# iPot.net
KiCad netlist of a schematic drawn in EAGLE
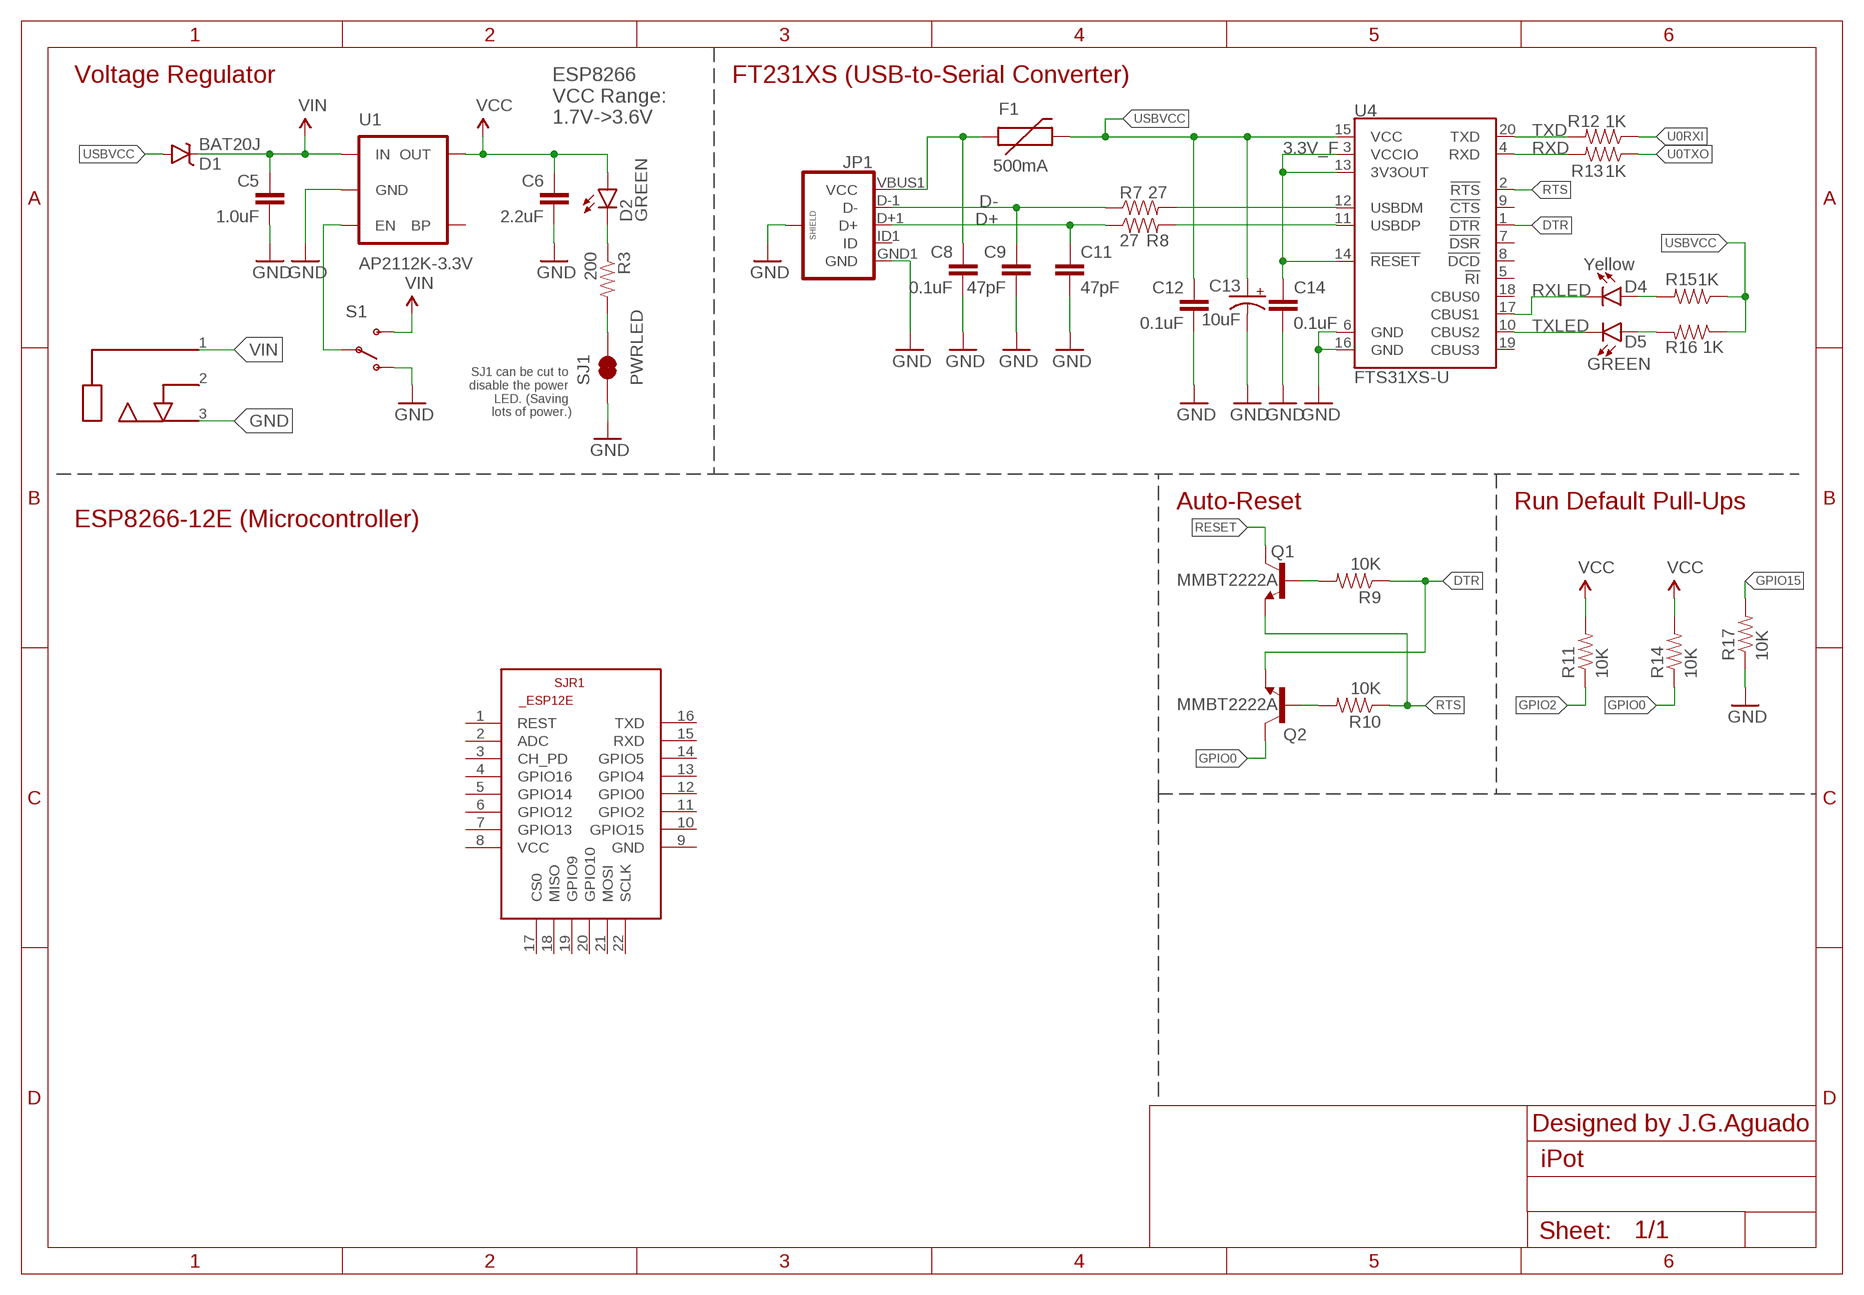
[diagram p0: schematic, sheet 1]

(export (version "E")
  (design (tool "Eeschema 10.0.6"))
  (components
    (comp (ref "C5")
      (value "1.0uF")
      (footprint "eagle-import:0805")
      (libsource (lib "eagle-import") (part "1.0UF-25V-+80/-20(0805)"))
    )
    (comp (ref "C6")
      (value "2.2uF")
      (footprint "eagle-import:0603-CAP")
      (libsource (lib "eagle-import") (part "2.2UF-10V-20%(0603)"))
    )
    (comp (ref "C8")
      (value "0.1uF")
      (footprint "eagle-import:0603-CAP")
      (libsource (lib "eagle-import") (part "0.1UF-25V(+80/-20%)(0603)"))
    )
    (comp (ref "C9")
      (value "47pF")
      (footprint "eagle-import:0603-CAP")
      (libsource (lib "eagle-import") (part "47PF-50V-5%(0603)"))
    )
    (comp (ref "C11")
      (value "47pF")
      (footprint "eagle-import:0603-CAP")
      (libsource (lib "eagle-import") (part "47PF-50V-5%(0603)"))
    )
    (comp (ref "C12")
      (value "0.1uF")
      (footprint "eagle-import:0603-CAP")
      (libsource (lib "eagle-import") (part "0.1UF-25V(+80/-20%)(0603)"))
    )
    (comp (ref "C13")
      (value "10uF")
      (footprint "eagle-import:EIA3216")
      (libsource (lib "eagle-import") (part "10UF-16V-10%(TANT)"))
    )
    (comp (ref "C14")
      (value "0.1uF")
      (footprint "eagle-import:0603-CAP")
      (libsource (lib "eagle-import") (part "0.1UF-25V(+80/-20%)(0603)"))
    )
    (comp (ref "D1")
      (value "BAT20J")
      (footprint "eagle-import:SOD-323")
      (libsource (lib "eagle-import") (part "DIODE-SCHOTTKY-BAT20J"))
    )
    (comp (ref "D2")
      (value "GREEN")
      (footprint "eagle-import:LED-0603")
      (libsource (lib "eagle-import") (part "LED-RED0603"))
    )
    (comp (ref "D4")
      (value "Yellow")
      (footprint "eagle-import:LED-0603")
      (libsource (lib "eagle-import") (part "LED-YELLOW0603"))
    )
    (comp (ref "D5")
      (value "GREEN")
      (footprint "eagle-import:LED-0603")
      (libsource (lib "eagle-import") (part "LED-GREEN0603"))
    )
    (comp (ref "F1")
      (value "500mA")
      (footprint "eagle-import:PTC-1206")
      (libsource (lib "eagle-import") (part "PTCSMD"))
    )
    (comp (ref "JP1")
      (value "USB_MICROB_PLUGCONN-11752")
      (footprint "eagle-import:USB-B-MICRO-SMD_V03")
      (libsource (lib "eagle-import") (part "USB_MICROB_PLUGCONN-11752"))
    )
    (comp (ref "JP2")
      (value "DC_JACK_1.3")
      (footprint "eagle-import:DC_JACK_1.3")
      (libsource (lib "eagle-import") (part "DC_JACK_1.3"))
    )
    (comp (ref "Q1")
      (value "MMBT2222A")
      (footprint "eagle-import:SOT23-3")
      (libsource (lib "eagle-import") (part "TRANSISTOR_NPNMMBT2222A"))
    )
    (comp (ref "Q2")
      (value "MMBT2222A")
      (footprint "eagle-import:SOT23-3")
      (libsource (lib "eagle-import") (part "TRANSISTOR_NPNMMBT2222A"))
    )
    (comp (ref "R3")
      (value "200")
      (footprint "eagle-import:0603-RES")
      (libsource (lib "eagle-import") (part "200OHM1/10W1%(0603)"))
    )
    (comp (ref "R7")
      (value "27")
      (footprint "eagle-import:0603-RES")
      (libsource (lib "eagle-import") (part "27OHM1/10W1%(0603)0603-RES"))
    )
    (comp (ref "R8")
      (value "27")
      (footprint "eagle-import:0603-RES")
      (libsource (lib "eagle-import") (part "27OHM1/10W1%(0603)0603-RES"))
    )
    (comp (ref "R9")
      (value "10K")
      (footprint "eagle-import:0603-RES")
      (libsource (lib "eagle-import") (part "10KOHM1/10W1%(0603)0603"))
    )
    (comp (ref "R10")
      (value "10K")
      (footprint "eagle-import:0603-RES")
      (libsource (lib "eagle-import") (part "10KOHM1/10W1%(0603)0603"))
    )
    (comp (ref "R11")
      (value "10K")
      (footprint "eagle-import:0603-RES")
      (libsource (lib "eagle-import") (part "10KOHM1/10W1%(0603)0603"))
    )
    (comp (ref "R12")
      (value "1K")
      (footprint "eagle-import:0603-RES")
      (libsource (lib "eagle-import") (part "1KOHM-1/10W-1%(0603)"))
    )
    (comp (ref "R13")
      (value "1K")
      (footprint "eagle-import:0603-RES")
      (libsource (lib "eagle-import") (part "1KOHM-1/10W-1%(0603)"))
    )
    (comp (ref "R14")
      (value "10K")
      (footprint "eagle-import:0603-RES")
      (libsource (lib "eagle-import") (part "10KOHM1/10W1%(0603)0603"))
    )
    (comp (ref "R15")
      (value "1K")
      (footprint "eagle-import:0603-RES")
      (libsource (lib "eagle-import") (part "1KOHM-1/10W-1%(0603)"))
    )
    (comp (ref "R16")
      (value "1K")
      (footprint "eagle-import:0603-RES")
      (libsource (lib "eagle-import") (part "1KOHM-1/10W-1%(0603)"))
    )
    (comp (ref "R17")
      (value "10K")
      (footprint "eagle-import:0603-RES")
      (libsource (lib "eagle-import") (part "10KOHM1/10W1%(0603)0603"))
    )
    (comp (ref "S1")
      (value "SWITCH-SPDT-SMD-A")
      (footprint "eagle-import:SWITCH-SPST-SMD-A")
      (libsource (lib "eagle-import") (part "SWITCH-SPDT-SMD-A"))
    )
    (comp (ref "SJ1")
      (value "PWRLED")
      (footprint "eagle-import:PAD-JUMPER-2-NC_BY_TRACE_YES_SILK")
      (libsource (lib "eagle-import") (part "JUMPER-PAD-2-NC_BY_TRACE"))
    )
    (comp (ref "SJR1")
      (value "ESP8266-12EESP12E")
      (footprint "eagle-import:ESP8266-ESP12E")
      (libsource (lib "eagle-import") (part "ESP8266-12EESP12E"))
    )
    (comp (ref "U1")
      (value "AP2112K-3.3V")
      (footprint "eagle-import:SOT23-5")
      (libsource (lib "eagle-import") (part "V_REG_LDOSMD"))
    )
    (comp (ref "U4")
      (value "FTS31XS-U")
      (footprint "eagle-import:SSOP20_L")
      (libsource (lib "eagle-import") (part "FT231XS"))
    )
  )
  (nets
    (net (code "1") (name "/3.3V_F") (class "Default")
      (node (ref "C14") (pin "1") (pinfunction "1_1") (pintype "passive"))
      (node (ref "U4") (pin "13") (pinfunction "3V3OUT_13") (pintype "bidirectional"))
      (node (ref "U4") (pin "14") (pinfunction "~{RESET}_14") (pintype "bidirectional"))
      (node (ref "U4") (pin "3") (pinfunction "VCCIO_3") (pintype "bidirectional"))
    )
    (net (code "2") (name "/D+") (class "Default")
      (node (ref "C11") (pin "1") (pinfunction "1_1") (pintype "passive"))
      (node (ref "JP1") (pin "D+1") (pinfunction "D+_D+1") (pintype "bidirectional"))
      (node (ref "R8") (pin "1") (pinfunction "1_1") (pintype "passive"))
    )
    (net (code "3") (name "/D-") (class "Default")
      (node (ref "C9") (pin "1") (pinfunction "1_1") (pintype "passive"))
      (node (ref "JP1") (pin "D-1") (pinfunction "D-_D-1") (pintype "bidirectional"))
      (node (ref "R7") (pin "1") (pinfunction "1_1") (pintype "passive"))
    )
    (net (code "4") (name "/RXD") (class "Default")
      (node (ref "R13") (pin "2") (pinfunction "2_2") (pintype "passive"))
      (node (ref "U4") (pin "4") (pinfunction "RXD_4") (pintype "bidirectional"))
    )
    (net (code "5") (name "/RXLED") (class "Default")
      (node (ref "D4") (pin "C") (pinfunction "C_C") (pintype "passive"))
      (node (ref "U4") (pin "17") (pinfunction "CBUS1_17") (pintype "bidirectional"))
    )
    (net (code "6") (name "/TXD") (class "Default")
      (node (ref "R12") (pin "2") (pinfunction "2_2") (pintype "passive"))
      (node (ref "U4") (pin "20") (pinfunction "TXD_20") (pintype "bidirectional"))
    )
    (net (code "7") (name "/TXLED") (class "Default")
      (node (ref "D5") (pin "C") (pinfunction "C_C") (pintype "passive"))
      (node (ref "U4") (pin "10") (pinfunction "CBUS2_10") (pintype "bidirectional"))
    )
    (net (code "8") (name "DTR") (class "Default")
      (node (ref "Q2") (pin "2") (pinfunction "E_2") (pintype "passive"))
      (node (ref "R9") (pin "1") (pinfunction "1_1") (pintype "passive"))
      (node (ref "U4") (pin "1") (pinfunction "~{DTR}_1") (pintype "bidirectional"))
    )
    (net (code "9") (name "GND") (class "Default")
      (node (ref "C11") (pin "2") (pinfunction "2_2") (pintype "passive"))
      (node (ref "C12") (pin "2") (pinfunction "2_2") (pintype "passive"))
      (node (ref "C13") (pin "C") (pinfunction "-_C") (pintype "passive"))
      (node (ref "C14") (pin "2") (pinfunction "2_2") (pintype "passive"))
      (node (ref "C5") (pin "2") (pinfunction "2_2") (pintype "passive"))
      (node (ref "C6") (pin "2") (pinfunction "2_2") (pintype "passive"))
      (node (ref "C8") (pin "2") (pinfunction "2_2") (pintype "passive"))
      (node (ref "C9") (pin "2") (pinfunction "2_2") (pintype "passive"))
      (node (ref "JP1") (pin "GND1") (pinfunction "GND_GND1") (pintype "bidirectional"))
      (node (ref "JP1") (pin "SHIELD1") (pinfunction "SHIELD_SHIELD1") (pintype "bidirectional"))
      (node (ref "JP1") (pin "SHIELD2") (pinfunction "SHIELD_SHIELD2") (pintype "bidirectional"))
      (node (ref "JP1") (pin "SHIELD3") (pinfunction "SHIELD_SHIELD3") (pintype "bidirectional"))
      (node (ref "JP2") (pin "3") (pinfunction "3_3") (pintype "bidirectional"))
      (node (ref "R17") (pin "1") (pinfunction "1_1") (pintype "passive"))
      (node (ref "S1") (pin "1") (pinfunction "O_1") (pintype "passive"))
      (node (ref "SJ1") (pin "1") (pinfunction "1_1") (pintype "passive"))
      (node (ref "U1") (pin "2") (pinfunction "GND_2") (pintype "input"))
      (node (ref "U4") (pin "16") (pinfunction "GND_16") (pintype "bidirectional"))
      (node (ref "U4") (pin "6") (pinfunction "GND_6") (pintype "bidirectional"))
    )
    (net (code "10") (name "GPIO0") (class "Default")
      (node (ref "Q2") (pin "3") (pinfunction "C_3") (pintype "passive"))
      (node (ref "R14") (pin "1") (pinfunction "1_1") (pintype "passive"))
    )
    (net (code "11") (name "GPIO2") (class "Default")
      (node (ref "R11") (pin "1") (pinfunction "1_1") (pintype "passive"))
    )
    (net (code "12") (name "GPIO15") (class "Default")
      (node (ref "R17") (pin "2") (pinfunction "2_2") (pintype "passive"))
    )
    (net (code "13") (name "Net-(D2-PadC)") (class "Default")
      (node (ref "D2") (pin "C") (pinfunction "C_C") (pintype "passive"))
      (node (ref "R3") (pin "1") (pinfunction "1_1") (pintype "passive"))
    )
    (net (code "14") (name "Net-(D4-PadA)") (class "Default")
      (node (ref "D4") (pin "A") (pinfunction "A_A") (pintype "passive"))
      (node (ref "R15") (pin "2") (pinfunction "2_2") (pintype "passive"))
    )
    (net (code "15") (name "Net-(D5-PadA)") (class "Default")
      (node (ref "D5") (pin "A") (pinfunction "A_A") (pintype "passive"))
      (node (ref "R16") (pin "2") (pinfunction "2_2") (pintype "passive"))
    )
    (net (code "16") (name "Net-(JP1-VCC)") (class "Default")
      (node (ref "C8") (pin "1") (pinfunction "1_1") (pintype "passive"))
      (node (ref "F1") (pin "1") (pinfunction "1_1") (pintype "bidirectional"))
      (node (ref "JP1") (pin "VBUS1") (pinfunction "VCC_VBUS1") (pintype "bidirectional"))
    )
    (net (code "17") (name "Net-(Q1-B)") (class "Default")
      (node (ref "Q1") (pin "1") (pinfunction "B_1") (pintype "passive"))
      (node (ref "R9") (pin "2") (pinfunction "2_2") (pintype "passive"))
    )
    (net (code "18") (name "Net-(Q2-B)") (class "Default")
      (node (ref "Q2") (pin "1") (pinfunction "B_1") (pintype "passive"))
      (node (ref "R10") (pin "2") (pinfunction "2_2") (pintype "passive"))
    )
    (net (code "19") (name "Net-(R3-Pad2)") (class "Default")
      (node (ref "R3") (pin "2") (pinfunction "2_2") (pintype "passive"))
      (node (ref "SJ1") (pin "2") (pinfunction "2_2") (pintype "passive"))
    )
    (net (code "20") (name "Net-(S1-P)") (class "Default")
      (node (ref "S1") (pin "2") (pinfunction "P_2") (pintype "passive"))
      (node (ref "U1") (pin "3") (pinfunction "EN_3") (pintype "input"))
    )
    (net (code "21") (name "Net-(U4-USBDM)") (class "Default")
      (node (ref "R7") (pin "2") (pinfunction "2_2") (pintype "passive"))
      (node (ref "U4") (pin "12") (pinfunction "USBDM_12") (pintype "bidirectional"))
    )
    (net (code "22") (name "Net-(U4-USBDP)") (class "Default")
      (node (ref "R8") (pin "2") (pinfunction "2_2") (pintype "passive"))
      (node (ref "U4") (pin "11") (pinfunction "USBDP_11") (pintype "bidirectional"))
    )
    (net (code "23") (name "RESET") (class "Default")
      (node (ref "Q1") (pin "3") (pinfunction "C_3") (pintype "passive"))
    )
    (net (code "24") (name "RTS") (class "Default")
      (node (ref "Q1") (pin "2") (pinfunction "E_2") (pintype "passive"))
      (node (ref "R10") (pin "1") (pinfunction "1_1") (pintype "passive"))
      (node (ref "U4") (pin "2") (pinfunction "~{RTS}_2") (pintype "bidirectional"))
    )
    (net (code "25") (name "U0RXI") (class "Default")
      (node (ref "R12") (pin "1") (pinfunction "1_1") (pintype "passive"))
    )
    (net (code "26") (name "U0TXO") (class "Default")
      (node (ref "R13") (pin "1") (pinfunction "1_1") (pintype "passive"))
    )
    (net (code "27") (name "USBVCC") (class "Default")
      (node (ref "C12") (pin "1") (pinfunction "1_1") (pintype "passive"))
      (node (ref "C13") (pin "A") (pinfunction "+_A") (pintype "passive"))
      (node (ref "D1") (pin "A") (pinfunction "A_A") (pintype "passive"))
      (node (ref "F1") (pin "2") (pinfunction "2_2") (pintype "bidirectional"))
      (node (ref "R15") (pin "1") (pinfunction "1_1") (pintype "passive"))
      (node (ref "R16") (pin "1") (pinfunction "1_1") (pintype "passive"))
      (node (ref "U4") (pin "15") (pinfunction "VCC_15") (pintype "bidirectional"))
    )
    (net (code "28") (name "VCC") (class "Default")
      (node (ref "C6") (pin "1") (pinfunction "1_1") (pintype "passive"))
      (node (ref "D2") (pin "A") (pinfunction "A_A") (pintype "passive"))
      (node (ref "R11") (pin "2") (pinfunction "2_2") (pintype "passive"))
      (node (ref "R14") (pin "2") (pinfunction "2_2") (pintype "passive"))
      (node (ref "U1") (pin "5") (pinfunction "OUT_5") (pintype "passive"))
    )
    (net (code "29") (name "VIN") (class "Default")
      (node (ref "C5") (pin "1") (pinfunction "1_1") (pintype "passive"))
      (node (ref "D1") (pin "C") (pinfunction "C_C") (pintype "passive"))
      (node (ref "JP2") (pin "1") (pinfunction "1_1") (pintype "bidirectional"))
      (node (ref "S1") (pin "3") (pinfunction "S_3") (pintype "passive"))
      (node (ref "U1") (pin "1") (pinfunction "IN_1") (pintype "input"))
    )
    (net (code "30") (name "unconnected-(JP1-ID-PadID1)") (class "Default")
      (node (ref "JP1") (pin "ID1") (pinfunction "ID_ID1") (pintype "bidirectional"))
    )
    (net (code "31") (name "unconnected-(JP2-Pad2)") (class "Default")
      (node (ref "JP2") (pin "2") (pinfunction "2_2") (pintype "bidirectional"))
    )
    (net (code "32") (name "unconnected-(SJR1-ADC-Pad2)") (class "Default")
      (node (ref "SJR1") (pin "2") (pinfunction "ADC_2") (pintype "bidirectional"))
    )
    (net (code "33") (name "unconnected-(SJR1-CH_PD-Pad3)") (class "Default")
      (node (ref "SJR1") (pin "3") (pinfunction "CH_PD_3") (pintype "bidirectional"))
    )
    (net (code "34") (name "unconnected-(SJR1-CS0-Pad17)") (class "Default")
      (node (ref "SJR1") (pin "17") (pinfunction "CS0_17") (pintype "bidirectional"))
    )
    (net (code "35") (name "unconnected-(SJR1-GND-Pad9)") (class "Default")
      (node (ref "SJR1") (pin "9") (pinfunction "GND_9") (pintype "bidirectional"))
    )
    (net (code "36") (name "unconnected-(SJR1-GPIO0-Pad12)") (class "Default")
      (node (ref "SJR1") (pin "12") (pinfunction "GPIO0_12") (pintype "bidirectional"))
    )
    (net (code "37") (name "unconnected-(SJR1-GPIO2-Pad11)") (class "Default")
      (node (ref "SJR1") (pin "11") (pinfunction "GPIO2_11") (pintype "bidirectional"))
    )
    (net (code "38") (name "unconnected-(SJR1-GPIO4-Pad13)") (class "Default")
      (node (ref "SJR1") (pin "13") (pinfunction "GPIO4_13") (pintype "bidirectional"))
    )
    (net (code "39") (name "unconnected-(SJR1-GPIO5-Pad14)") (class "Default")
      (node (ref "SJR1") (pin "14") (pinfunction "GPIO5_14") (pintype "bidirectional"))
    )
    (net (code "40") (name "unconnected-(SJR1-GPIO9-Pad19)") (class "Default")
      (node (ref "SJR1") (pin "19") (pinfunction "GPIO9_19") (pintype "bidirectional"))
    )
    (net (code "41") (name "unconnected-(SJR1-GPIO10-Pad20)") (class "Default")
      (node (ref "SJR1") (pin "20") (pinfunction "GPIO10_20") (pintype "bidirectional"))
    )
    (net (code "42") (name "unconnected-(SJR1-GPIO12-Pad6)") (class "Default")
      (node (ref "SJR1") (pin "6") (pinfunction "GPIO12_6") (pintype "bidirectional"))
    )
    (net (code "43") (name "unconnected-(SJR1-GPIO13-Pad7)") (class "Default")
      (node (ref "SJR1") (pin "7") (pinfunction "GPIO13_7") (pintype "bidirectional"))
    )
    (net (code "44") (name "unconnected-(SJR1-GPIO14-Pad5)") (class "Default")
      (node (ref "SJR1") (pin "5") (pinfunction "GPIO14_5") (pintype "bidirectional"))
    )
    (net (code "45") (name "unconnected-(SJR1-GPIO15-Pad10)") (class "Default")
      (node (ref "SJR1") (pin "10") (pinfunction "GPIO15_10") (pintype "bidirectional"))
    )
    (net (code "46") (name "unconnected-(SJR1-GPIO16-Pad4)") (class "Default")
      (node (ref "SJR1") (pin "4") (pinfunction "GPIO16_4") (pintype "bidirectional"))
    )
    (net (code "47") (name "unconnected-(SJR1-MISO-Pad18)") (class "Default")
      (node (ref "SJR1") (pin "18") (pinfunction "MISO_18") (pintype "bidirectional"))
    )
    (net (code "48") (name "unconnected-(SJR1-MOSI-Pad21)") (class "Default")
      (node (ref "SJR1") (pin "21") (pinfunction "MOSI_21") (pintype "bidirectional"))
    )
    (net (code "49") (name "unconnected-(SJR1-REST-Pad1)") (class "Default")
      (node (ref "SJR1") (pin "1") (pinfunction "REST_1") (pintype "bidirectional"))
    )
    (net (code "50") (name "unconnected-(SJR1-RXD-Pad15)") (class "Default")
      (node (ref "SJR1") (pin "15") (pinfunction "RXD_15") (pintype "bidirectional"))
    )
    (net (code "51") (name "unconnected-(SJR1-SCLK-Pad22)") (class "Default")
      (node (ref "SJR1") (pin "22") (pinfunction "SCLK_22") (pintype "bidirectional"))
    )
    (net (code "52") (name "unconnected-(SJR1-TXD-Pad16)") (class "Default")
      (node (ref "SJR1") (pin "16") (pinfunction "TXD_16") (pintype "bidirectional"))
    )
    (net (code "53") (name "unconnected-(SJR1-VCC-Pad8)") (class "Default")
      (node (ref "SJR1") (pin "8") (pinfunction "VCC_8") (pintype "bidirectional"))
    )
    (net (code "54") (name "unconnected-(U1-BP-Pad4)") (class "Default")
      (node (ref "U1") (pin "4") (pinfunction "BP_4") (pintype "input"))
    )
    (net (code "55") (name "unconnected-(U4-CBUS0-Pad18)") (class "Default")
      (node (ref "U4") (pin "18") (pinfunction "CBUS0_18") (pintype "bidirectional"))
    )
    (net (code "56") (name "unconnected-(U4-CBUS3-Pad19)") (class "Default")
      (node (ref "U4") (pin "19") (pinfunction "CBUS3_19") (pintype "bidirectional"))
    )
    (net (code "57") (name "unconnected-(U4-~{CTS}-Pad9)") (class "Default")
      (node (ref "U4") (pin "9") (pinfunction "~{CTS}_9") (pintype "bidirectional"))
    )
    (net (code "58") (name "unconnected-(U4-~{DCD}-Pad8)") (class "Default")
      (node (ref "U4") (pin "8") (pinfunction "~{DCD}_8") (pintype "bidirectional"))
    )
    (net (code "59") (name "unconnected-(U4-~{DSR}-Pad7)") (class "Default")
      (node (ref "U4") (pin "7") (pinfunction "~{DSR}_7") (pintype "bidirectional"))
    )
    (net (code "60") (name "unconnected-(U4-~{RI}-Pad5)") (class "Default")
      (node (ref "U4") (pin "5") (pinfunction "~{RI}_5") (pintype "bidirectional"))
    )
  )
)
